# SCH_CuboLab_2025-02-06.net
KiCad netlist of a schematic drawn in EasyEDA
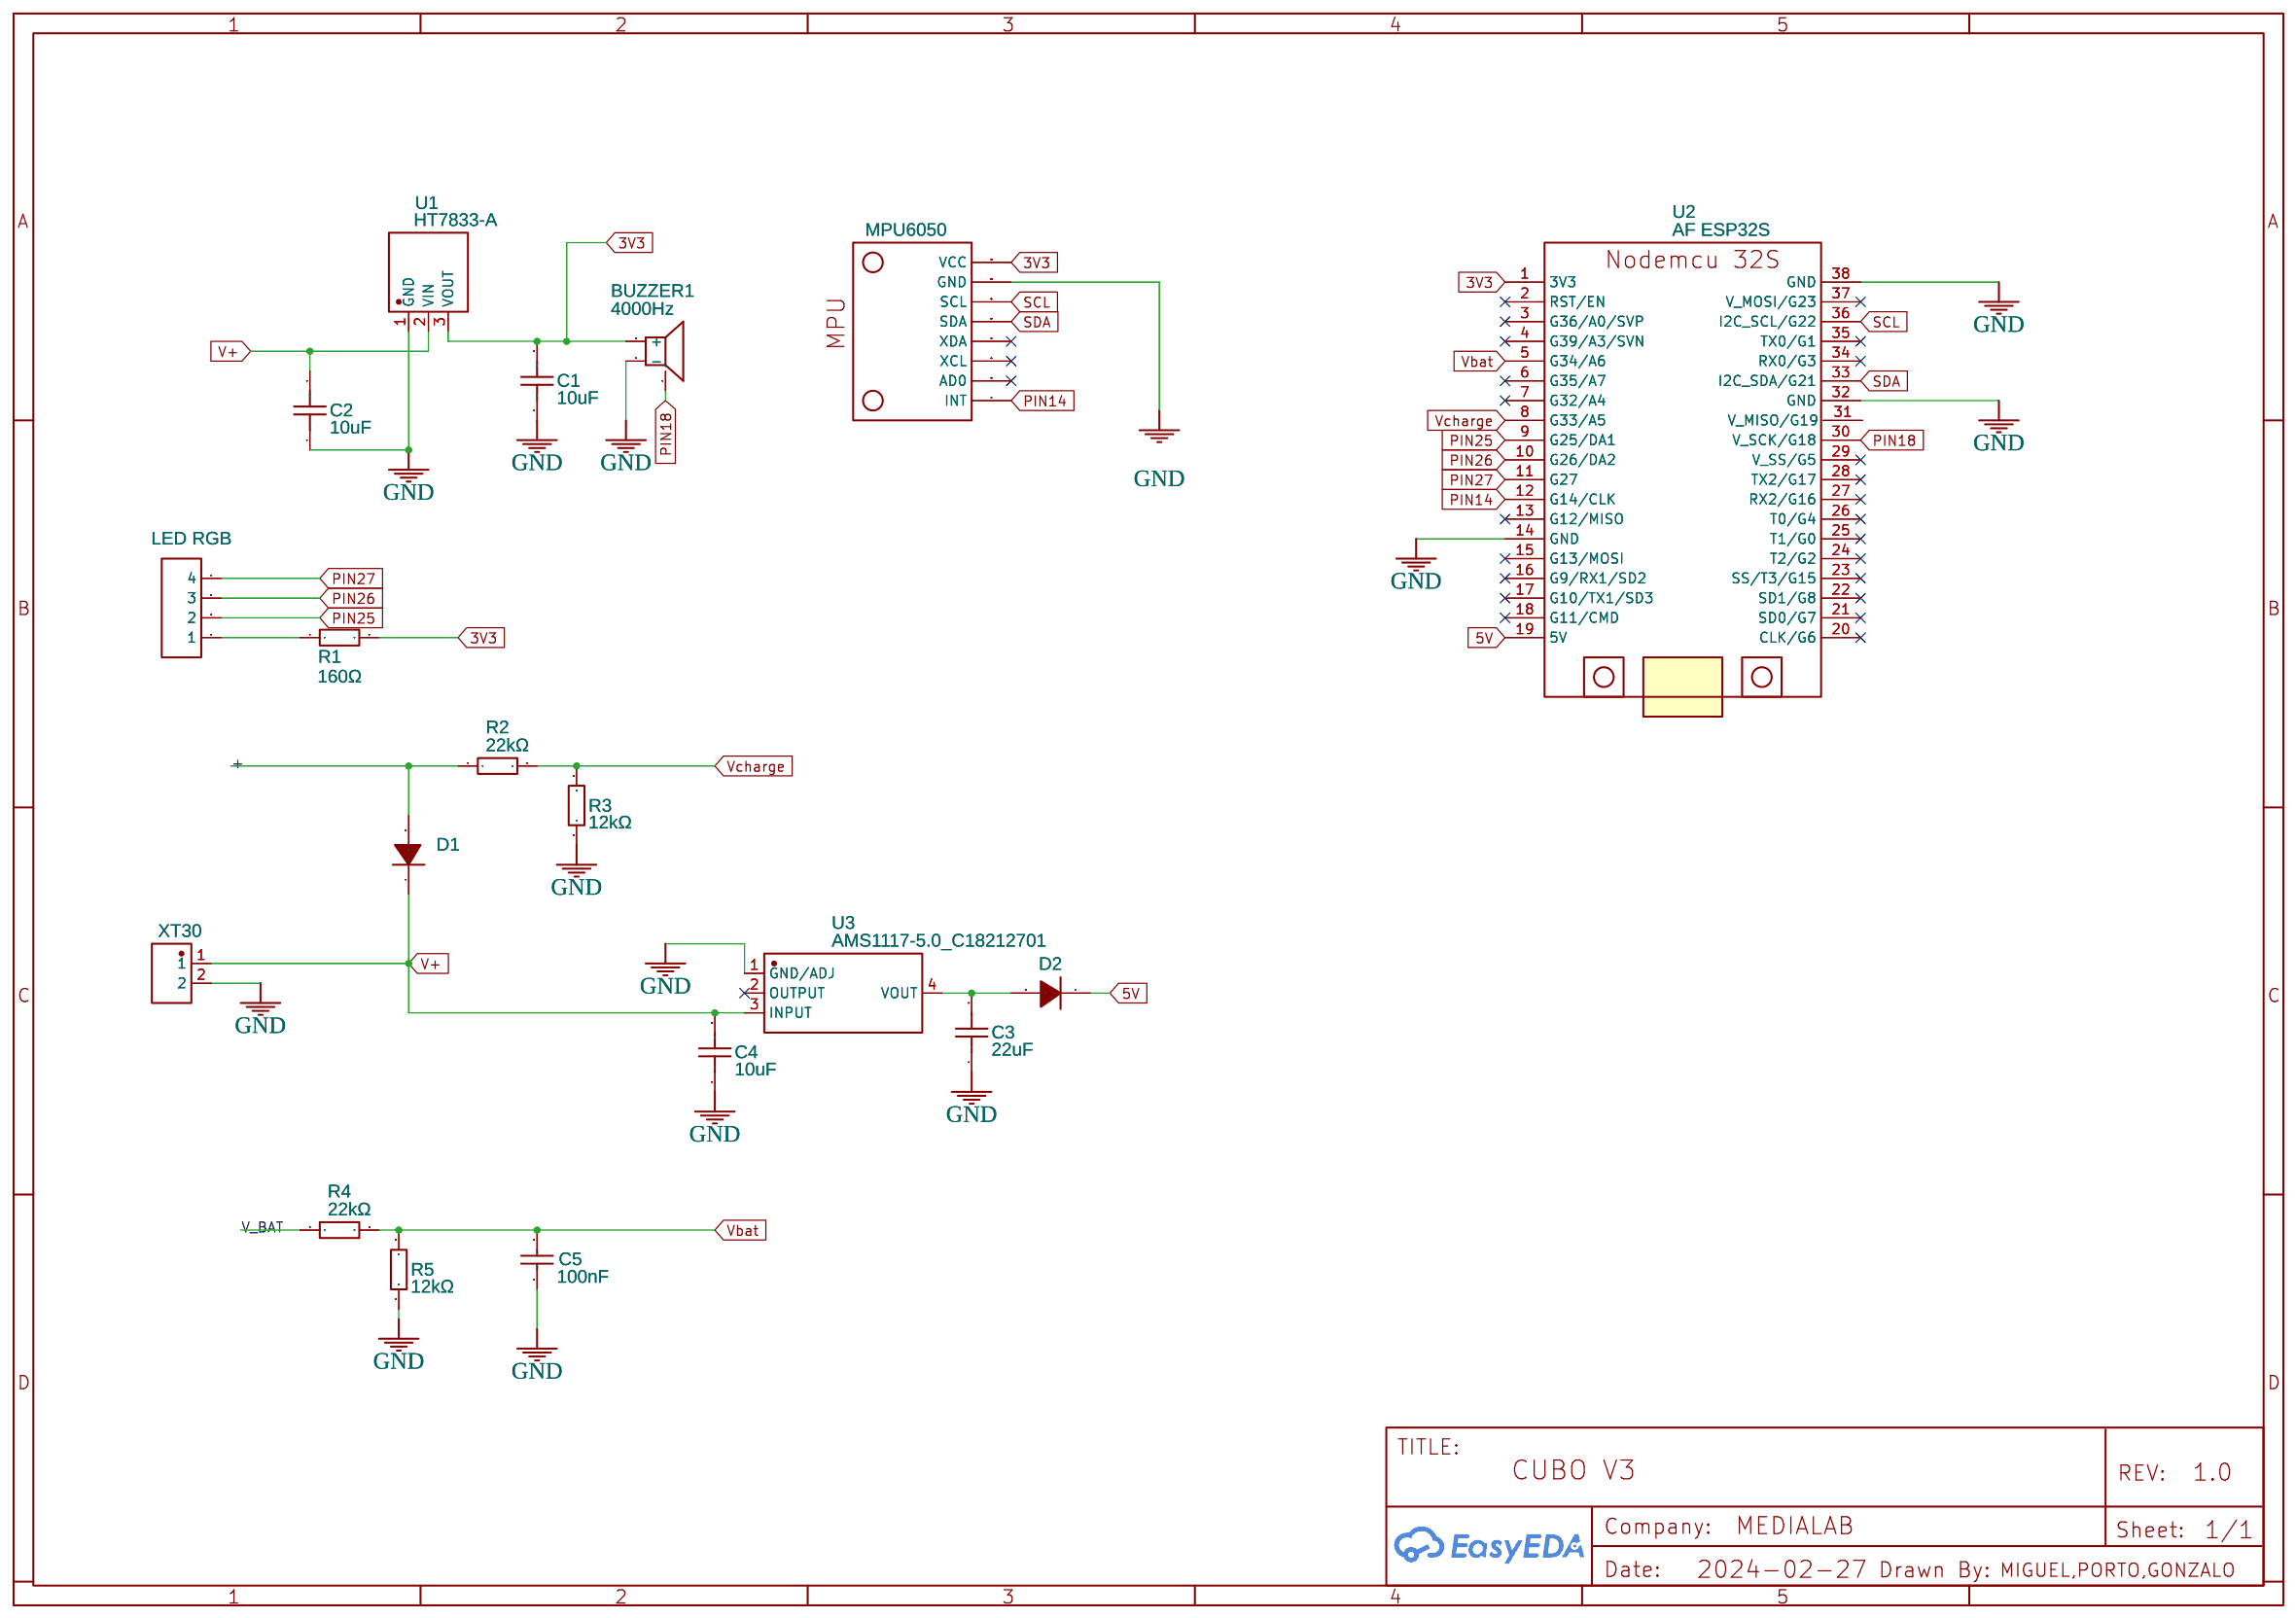
[diagram p0: schematic sheet]

(export (version "E")
  (design (tool "Eeschema 10.0.6"))
  (components
    (comp (ref "BUZZER1")
      (value "4000Hz")
      (fields (field (name "Manufacturer Part") "MLT-5030") (field (name "Manufacturer") "华能"))
      (libsource (lib "") (part "MLT-5030"))
    )
    (comp (ref "C1")
      (value "10uF")
      (fields
        (field (name "Manufacturer Part") "CL21A106KOQNNNE")
        (field (name "Manufacturer") "SAMSUNG(三星)")
      )
      (libsource (lib "") (part "CS2012X7R105K500NRE"))
    )
    (comp (ref "C2")
      (value "10uF")
      (fields
        (field (name "Manufacturer Part") "CL21A106KOQNNNE")
        (field (name "Manufacturer") "SAMSUNG(三星)")
      )
      (libsource (lib "") (part "CS2012X7R105K500NRE"))
    )
    (comp (ref "C3")
      (value "22uF")
      (fields
        (field (name "Manufacturer Part") "CL21A226MPQNNNE")
        (field (name "Manufacturer") "SAMSUNG(三星)")
      )
      (libsource (lib "") (part "CS2012X7R105K500NRE"))
    )
    (comp (ref "C4")
      (value "10uF")
      (fields
        (field (name "Manufacturer Part") "CL21A106KOQNNNE")
        (field (name "Manufacturer") "SAMSUNG(三星)")
      )
      (libsource (lib "") (part "CS2012X7R105K500NRE"))
    )
    (comp (ref "C5")
      (value "100nF")
      (fields
        (field (name "Manufacturer Part") "CL21B104KBCNNNC")
        (field (name "Manufacturer") "SAMSUNG(三星)")
      )
      (libsource (lib "") (part "CL21B104KBCNNNC"))
    )
    (comp (ref "CN1")
      (value "XT30")
      (fields (field (name "Manufacturer Part") "XT30U-M") (field (name "Manufacturer") "AMASS(艾迈斯)"))
      (libsource (lib "") (part "XT30U-M"))
    )
    (comp (ref "D1")
      (value "PSBD1DF40V2H")
      (fields (field (name "Manufacturer") "Prisemi(芯导)"))
      (libsource (lib "") (part "PSBD1DF40V2H"))
    )
    (comp (ref "D2")
      (value "PSBD1DF40V2H")
      (fields (field (name "Manufacturer") "Prisemi(芯导)"))
      (libsource (lib "") (part "PSBD1DF40V2H_1"))
    )
    (comp (ref "H1") (value "LED RGB") (libsource (lib "") (part "Header 4")))
    (comp (ref "MPU6050") (value "MPU6050") (libsource (lib "") (part "MPU6050")))
    (comp (ref "R1")
      (value "160Ω")
      (fields
        (field (name "Manufacturer Part") "0805W8F1600T5E")
        (field (name "Manufacturer") "UNI-ROYAL(厚声)")
      )
      (libsource (lib "") (part "0805W8F1600T5E"))
    )
    (comp (ref "R2")
      (value "22kΩ")
      (fields
        (field (name "Manufacturer Part") "0805W8F2202T5E")
        (field (name "Manufacturer") "UNI-ROYAL(厚声)")
      )
      (libsource (lib "") (part "0805W8F2202T5E"))
    )
    (comp (ref "R3")
      (value "12kΩ")
      (fields
        (field (name "Manufacturer Part") "0805W8F1202T5E")
        (field (name "Manufacturer") "UNI-ROYAL(厚声)")
      )
      (libsource (lib "") (part "0805W8F1202T5E"))
    )
    (comp (ref "R4")
      (value "22kΩ")
      (fields
        (field (name "Manufacturer Part") "0805W8F2202T5E")
        (field (name "Manufacturer") "UNI-ROYAL(厚声)")
      )
      (libsource (lib "") (part "0805W8F2202T5E"))
    )
    (comp (ref "R5")
      (value "12kΩ")
      (fields
        (field (name "Manufacturer Part") "0805W8F1202T5E")
        (field (name "Manufacturer") "UNI-ROYAL(厚声)")
      )
      (libsource (lib "") (part "0805W8F1202T5E"))
    )
    (comp (ref "U1")
      (value "HT7833-A")
      (fields (field (name "Manufacturer") "UMW(友台半导体)"))
      (libsource (lib "") (part "HT7833-A"))
    )
    (comp (ref "U2")
      (value "AF ESP32S")
      (fields (field (name "Manufacturer Part") "NodeMCU ESP32S"))
      (libsource (lib "") (part "AF ESP32S"))
    )
    (comp (ref "U3")
      (value "AMS1117-5.0_C18212701")
      (fields
        (field (name "Manufacturer Part") "AMS1117-5.0")
        (field (name "Manufacturer") "TECH PUBLIC(台舟)")
      )
      (libsource (lib "") (part "AMS1117-5.0_C18212701"))
    )
  )
  (nets
    (net (code "1") (name "/+") (class "Default")
      (node (ref "D1") (pin "2") (pinfunction "+_2") (pintype "unspecified"))
      (node (ref "R2") (pin "1") (pinfunction "1_1") (pintype "input"))
    )
    (net (code "2") (name "/V_BAT") (class "Default")
      (node (ref "R4") (pin "1") (pinfunction "1_1") (pintype "input"))
    )
    (net (code "3") (name "3V3") (class "Default")
      (node (ref "BUZZER1") (pin "2") (pinfunction "+_2") (pintype "unspecified"))
      (node (ref "C1") (pin "2") (pinfunction "2_2") (pintype "unspecified"))
      (node (ref "MPU6050") (pin "VCC") (pinfunction "VCC_VCC") (pintype "unspecified"))
      (node (ref "R1") (pin "2") (pinfunction "2_2") (pintype "input"))
      (node (ref "U1") (pin "3") (pinfunction "VOUT_3") (pintype "unspecified"))
      (node (ref "U2") (pin "1") (pinfunction "3V3_1") (pintype "passive"))
    )
    (net (code "4") (name "5V") (class "Default")
      (node (ref "D2") (pin "1") (pinfunction "-_1") (pintype "unspecified"))
      (node (ref "U2") (pin "19") (pinfunction "5V_19") (pintype "passive"))
    )
    (net (code "5") (name "GND") (class "Default")
      (node (ref "BUZZER1") (pin "3") (pinfunction "-_3") (pintype "unspecified"))
      (node (ref "C1") (pin "1") (pinfunction "1_1") (pintype "unspecified"))
      (node (ref "C2") (pin "1") (pinfunction "1_1") (pintype "unspecified"))
      (node (ref "C3") (pin "1") (pinfunction "1_1") (pintype "unspecified"))
      (node (ref "C4") (pin "1") (pinfunction "1_1") (pintype "unspecified"))
      (node (ref "C5") (pin "1") (pinfunction "1_1") (pintype "input"))
      (node (ref "CN1") (pin "2") (pinfunction "2_2") (pintype "unspecified"))
      (node (ref "MPU6050") (pin "GND") (pinfunction "GND_GND") (pintype "unspecified"))
      (node (ref "R3") (pin "1") (pinfunction "1_1") (pintype "input"))
      (node (ref "R5") (pin "1") (pinfunction "1_1") (pintype "input"))
      (node (ref "U1") (pin "1") (pinfunction "GND_1") (pintype "unspecified"))
      (node (ref "U2") (pin "14") (pinfunction "GND_14") (pintype "passive"))
      (node (ref "U2") (pin "32") (pinfunction "GND_32") (pintype "passive"))
      (node (ref "U2") (pin "38") (pinfunction "GND_38") (pintype "passive"))
      (node (ref "U3") (pin "1") (pinfunction "GND/ADJ_1") (pintype "unspecified"))
    )
    (net (code "6") (name "Net-(D2-+)") (class "Default")
      (node (ref "C3") (pin "2") (pinfunction "2_2") (pintype "unspecified"))
      (node (ref "D2") (pin "2") (pinfunction "+_2") (pintype "unspecified"))
      (node (ref "U3") (pin "4") (pinfunction "VOUT_4") (pintype "unspecified"))
    )
    (net (code "7") (name "Net-(H1-Pad1)") (class "Default")
      (node (ref "H1") (pin "1") (pinfunction "1_1") (pintype "unspecified"))
      (node (ref "R1") (pin "1") (pinfunction "1_1") (pintype "input"))
    )
    (net (code "8") (name "PIN14") (class "Default")
      (node (ref "MPU6050") (pin "INT") (pinfunction "INT_INT") (pintype "unspecified"))
      (node (ref "U2") (pin "12") (pinfunction "G14/CLK_12") (pintype "bidirectional"))
    )
    (net (code "9") (name "PIN18") (class "Default")
      (node (ref "BUZZER1") (pin "1") (pinfunction "NC_1") (pintype "unspecified"))
      (node (ref "U2") (pin "30") (pinfunction "V_SCK/G18_30") (pintype "bidirectional"))
    )
    (net (code "10") (name "PIN25") (class "Default")
      (node (ref "H1") (pin "2") (pinfunction "2_2") (pintype "unspecified"))
      (node (ref "U2") (pin "9") (pinfunction "G25/DA1_9") (pintype "bidirectional"))
    )
    (net (code "11") (name "PIN26") (class "Default")
      (node (ref "H1") (pin "3") (pinfunction "3_3") (pintype "unspecified"))
      (node (ref "U2") (pin "10") (pinfunction "G26/DA2_10") (pintype "bidirectional"))
    )
    (net (code "12") (name "PIN27") (class "Default")
      (node (ref "H1") (pin "4") (pinfunction "4_4") (pintype "unspecified"))
      (node (ref "U2") (pin "11") (pinfunction "G27_11") (pintype "bidirectional"))
    )
    (net (code "13") (name "SCL") (class "Default")
      (node (ref "MPU6050") (pin "SCL") (pinfunction "SCL_SCL") (pintype "unspecified"))
      (node (ref "U2") (pin "36") (pinfunction "I2C_SCL/G22_36") (pintype "bidirectional"))
    )
    (net (code "14") (name "SDA") (class "Default")
      (node (ref "MPU6050") (pin "SDA") (pinfunction "SDA_SDA") (pintype "unspecified"))
      (node (ref "U2") (pin "33") (pinfunction "I2C_SDA/G21_33") (pintype "bidirectional"))
    )
    (net (code "15") (name "V+") (class "Default")
      (node (ref "C2") (pin "2") (pinfunction "2_2") (pintype "unspecified"))
      (node (ref "C4") (pin "2") (pinfunction "2_2") (pintype "unspecified"))
      (node (ref "CN1") (pin "1") (pinfunction "1_1") (pintype "unspecified"))
      (node (ref "D1") (pin "1") (pinfunction "-_1") (pintype "unspecified"))
      (node (ref "U1") (pin "2") (pinfunction "VIN_2") (pintype "unspecified"))
      (node (ref "U3") (pin "3") (pinfunction "INPUT_3") (pintype "unspecified"))
    )
    (net (code "16") (name "Vbat") (class "Default")
      (node (ref "C5") (pin "2") (pinfunction "2_2") (pintype "input"))
      (node (ref "R4") (pin "2") (pinfunction "2_2") (pintype "input"))
      (node (ref "R5") (pin "2") (pinfunction "2_2") (pintype "input"))
      (node (ref "U2") (pin "5") (pinfunction "G34/A6_5") (pintype "bidirectional"))
    )
    (net (code "17") (name "Vcharge") (class "Default")
      (node (ref "R2") (pin "2") (pinfunction "2_2") (pintype "input"))
      (node (ref "R3") (pin "2") (pinfunction "2_2") (pintype "input"))
      (node (ref "U2") (pin "8") (pinfunction "G33/A5_8") (pintype "bidirectional"))
    )
    (net (code "18") (name "unconnected-(MPU6050-PadAD0)") (class "Default")
      (node (ref "MPU6050") (pin "AD0") (pinfunction "AD0_AD0") (pintype "unspecified+no_connect"))
    )
    (net (code "19") (name "unconnected-(MPU6050-PadXCL)") (class "Default")
      (node (ref "MPU6050") (pin "XCL") (pinfunction "XCL_XCL") (pintype "unspecified+no_connect"))
    )
    (net (code "20") (name "unconnected-(MPU6050-PadXDA)") (class "Default")
      (node (ref "MPU6050") (pin "XDA") (pinfunction "XDA_XDA") (pintype "unspecified+no_connect"))
    )
    (net (code "21") (name "unconnected-(U2-CLK{slash}G6-Pad20)") (class "Default")
      (node (ref "U2") (pin "20") (pinfunction "CLK/G6_20") (pintype "bidirectional+no_connect"))
    )
    (net (code "22") (name "unconnected-(U2-G9{slash}RX1{slash}SD2-Pad16)") (class "Default")
      (node (ref "U2") (pin "16") (pinfunction "G9/RX1/SD2_16") (pintype "bidirectional+no_connect"))
    )
    (net (code "23") (name "unconnected-(U2-G10{slash}TX1{slash}SD3-Pad17)") (class "Default")
      (node (ref "U2") (pin "17") (pinfunction "G10/TX1/SD3_17") (pintype "bidirectional+no_connect"))
    )
    (net (code "24") (name "unconnected-(U2-G11{slash}CMD-Pad18)") (class "Default")
      (node (ref "U2") (pin "18") (pinfunction "G11/CMD_18") (pintype "bidirectional+no_connect"))
    )
    (net (code "25") (name "unconnected-(U2-G12{slash}MISO-Pad13)") (class "Default")
      (node (ref "U2") (pin "13") (pinfunction "G12/MISO_13") (pintype "bidirectional+no_connect"))
    )
    (net (code "26") (name "unconnected-(U2-G13{slash}MOSI-Pad15)") (class "Default")
      (node (ref "U2") (pin "15") (pinfunction "G13/MOSI_15") (pintype "bidirectional+no_connect"))
    )
    (net (code "27") (name "unconnected-(U2-G32{slash}A4-Pad7)") (class "Default")
      (node (ref "U2") (pin "7") (pinfunction "G32/A4_7") (pintype "bidirectional+no_connect"))
    )
    (net (code "28") (name "unconnected-(U2-G35{slash}A7-Pad6)") (class "Default")
      (node (ref "U2") (pin "6") (pinfunction "G35/A7_6") (pintype "bidirectional+no_connect"))
    )
    (net (code "29") (name "unconnected-(U2-G36{slash}A0{slash}SVP-Pad3)") (class "Default")
      (node (ref "U2") (pin "3") (pinfunction "G36/A0/SVP_3") (pintype "bidirectional+no_connect"))
    )
    (net (code "30") (name "unconnected-(U2-G39{slash}A3{slash}SVN-Pad4)") (class "Default")
      (node (ref "U2") (pin "4") (pinfunction "G39/A3/SVN_4") (pintype "bidirectional+no_connect"))
    )
    (net (code "31") (name "unconnected-(U2-RST{slash}EN-Pad2)") (class "Default")
      (node (ref "U2") (pin "2") (pinfunction "RST/EN_2") (pintype "bidirectional+no_connect"))
    )
    (net (code "32") (name "unconnected-(U2-RX0{slash}G3-Pad34)") (class "Default")
      (node (ref "U2") (pin "34") (pinfunction "RX0/G3_34") (pintype "bidirectional+no_connect"))
    )
    (net (code "33") (name "unconnected-(U2-RX2{slash}G16-Pad27)") (class "Default")
      (node (ref "U2") (pin "27") (pinfunction "RX2/G16_27") (pintype "bidirectional+no_connect"))
    )
    (net (code "34") (name "unconnected-(U2-SD0{slash}G7-Pad21)") (class "Default")
      (node (ref "U2") (pin "21") (pinfunction "SD0/G7_21") (pintype "bidirectional+no_connect"))
    )
    (net (code "35") (name "unconnected-(U2-SD1{slash}G8-Pad22)") (class "Default")
      (node (ref "U2") (pin "22") (pinfunction "SD1/G8_22") (pintype "bidirectional+no_connect"))
    )
    (net (code "36") (name "unconnected-(U2-SS{slash}T3{slash}G15-Pad23)") (class "Default")
      (node (ref "U2") (pin "23") (pinfunction "SS/T3/G15_23") (pintype "bidirectional+no_connect"))
    )
    (net (code "37") (name "unconnected-(U2-T0{slash}G4-Pad26)") (class "Default")
      (node (ref "U2") (pin "26") (pinfunction "T0/G4_26") (pintype "bidirectional+no_connect"))
    )
    (net (code "38") (name "unconnected-(U2-T1{slash}G0-Pad25)") (class "Default")
      (node (ref "U2") (pin "25") (pinfunction "T1/G0_25") (pintype "bidirectional+no_connect"))
    )
    (net (code "39") (name "unconnected-(U2-T2{slash}G2-Pad24)") (class "Default")
      (node (ref "U2") (pin "24") (pinfunction "T2/G2_24") (pintype "bidirectional+no_connect"))
    )
    (net (code "40") (name "unconnected-(U2-TX0{slash}G1-Pad35)") (class "Default")
      (node (ref "U2") (pin "35") (pinfunction "TX0/G1_35") (pintype "bidirectional+no_connect"))
    )
    (net (code "41") (name "unconnected-(U2-TX2{slash}G17-Pad28)") (class "Default")
      (node (ref "U2") (pin "28") (pinfunction "TX2/G17_28") (pintype "bidirectional+no_connect"))
    )
    (net (code "42") (name "unconnected-(U2-V_MISO{slash}G19-Pad31)") (class "Default")
      (node (ref "U2") (pin "31") (pinfunction "V_MISO/G19_31") (pintype "bidirectional"))
    )
    (net (code "43") (name "unconnected-(U2-V_MOSI{slash}G23-Pad37)") (class "Default")
      (node (ref "U2") (pin "37") (pinfunction "V_MOSI/G23_37") (pintype "bidirectional+no_connect"))
    )
    (net (code "44") (name "unconnected-(U2-V_SS{slash}G5-Pad29)") (class "Default")
      (node (ref "U2") (pin "29") (pinfunction "V_SS/G5_29") (pintype "bidirectional+no_connect"))
    )
    (net (code "45") (name "unconnected-(U3-OUTPUT-Pad2)") (class "Default")
      (node (ref "U3") (pin "2") (pinfunction "OUTPUT_2") (pintype "unspecified+no_connect"))
    )
  )
)
